# AJH_2b_v1_03.net
KiCad netlist of a schematic drawn in EAGLE
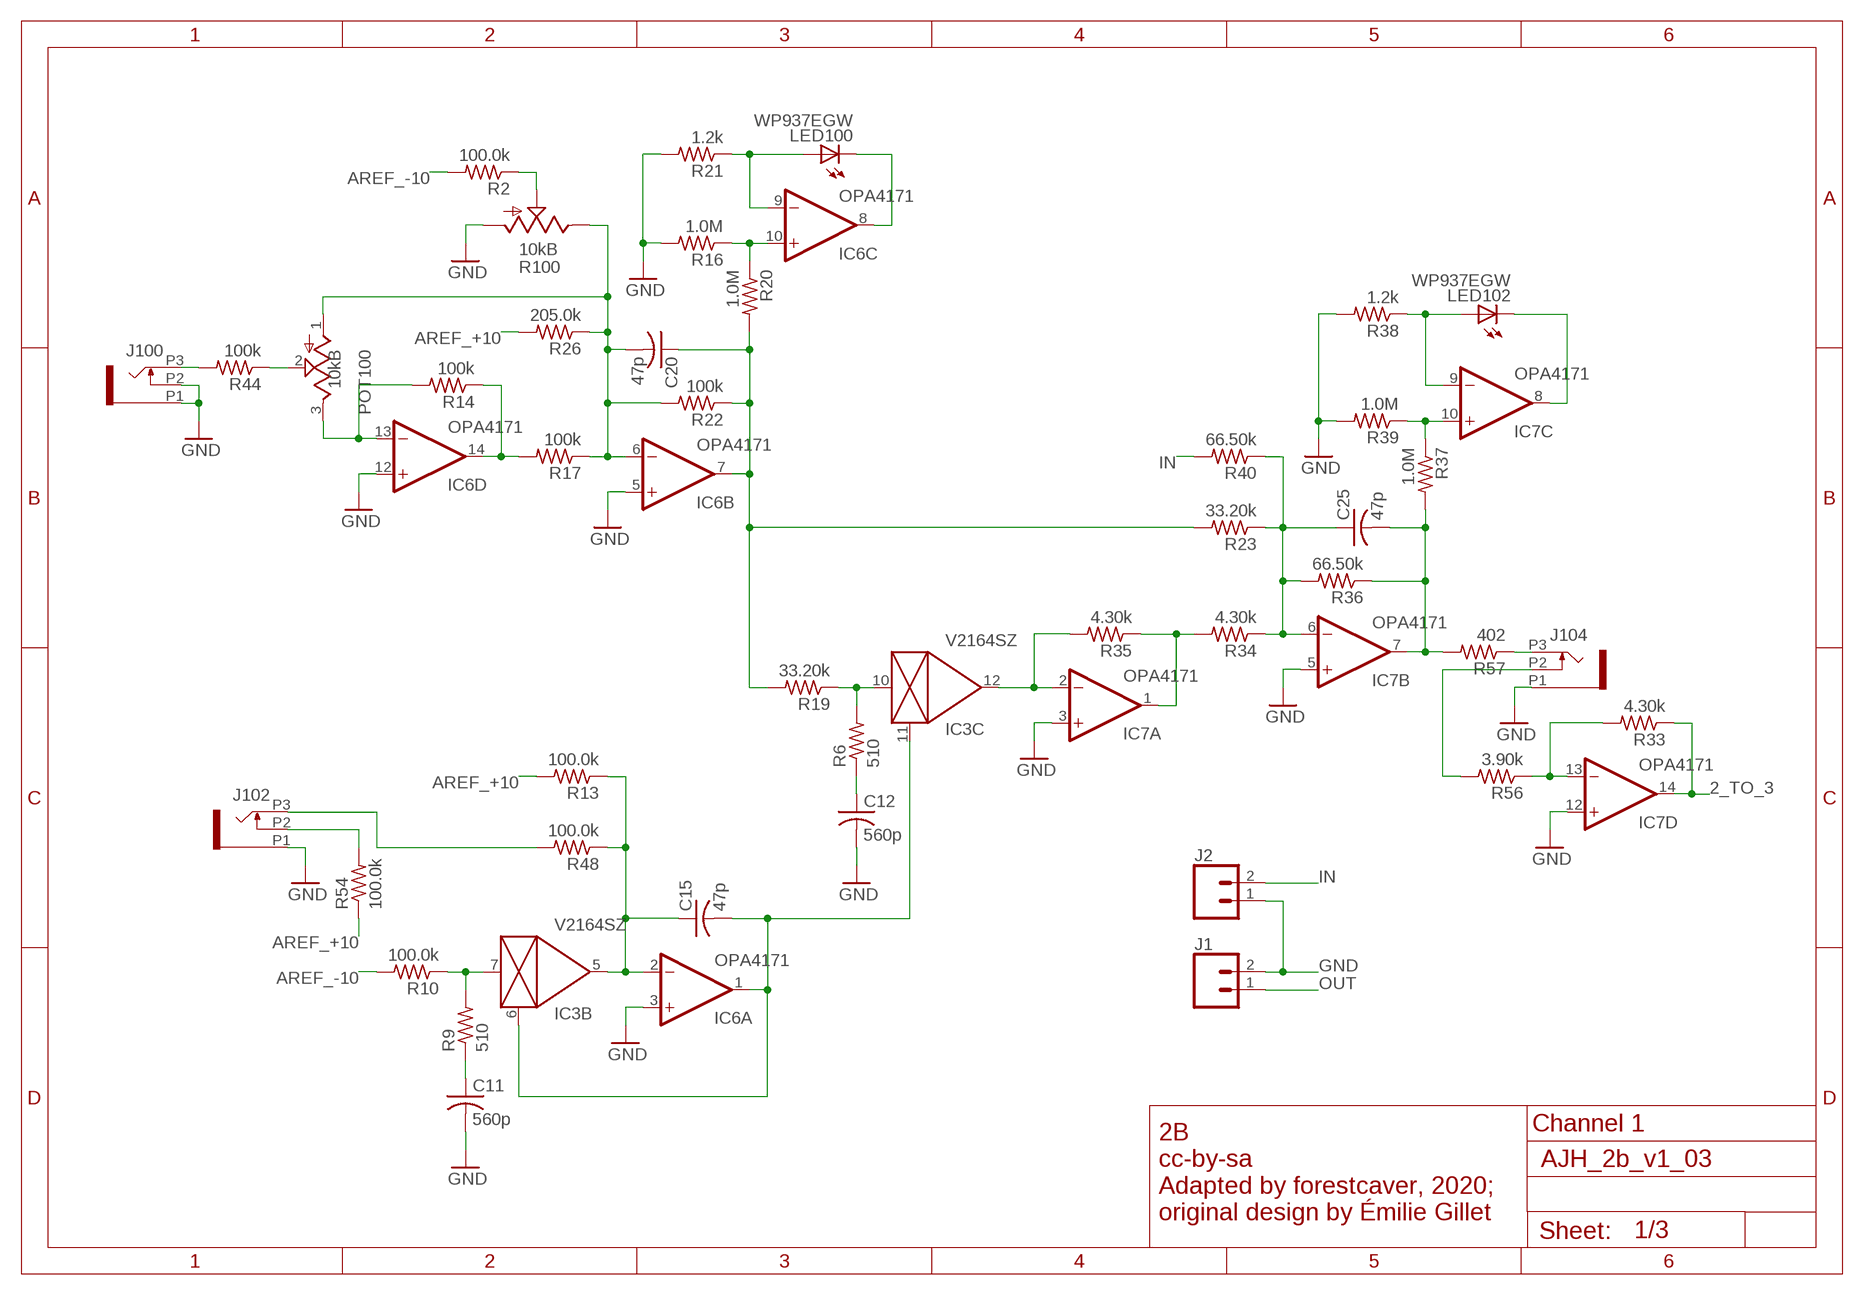
[diagram p0: schematic, sheet 1]
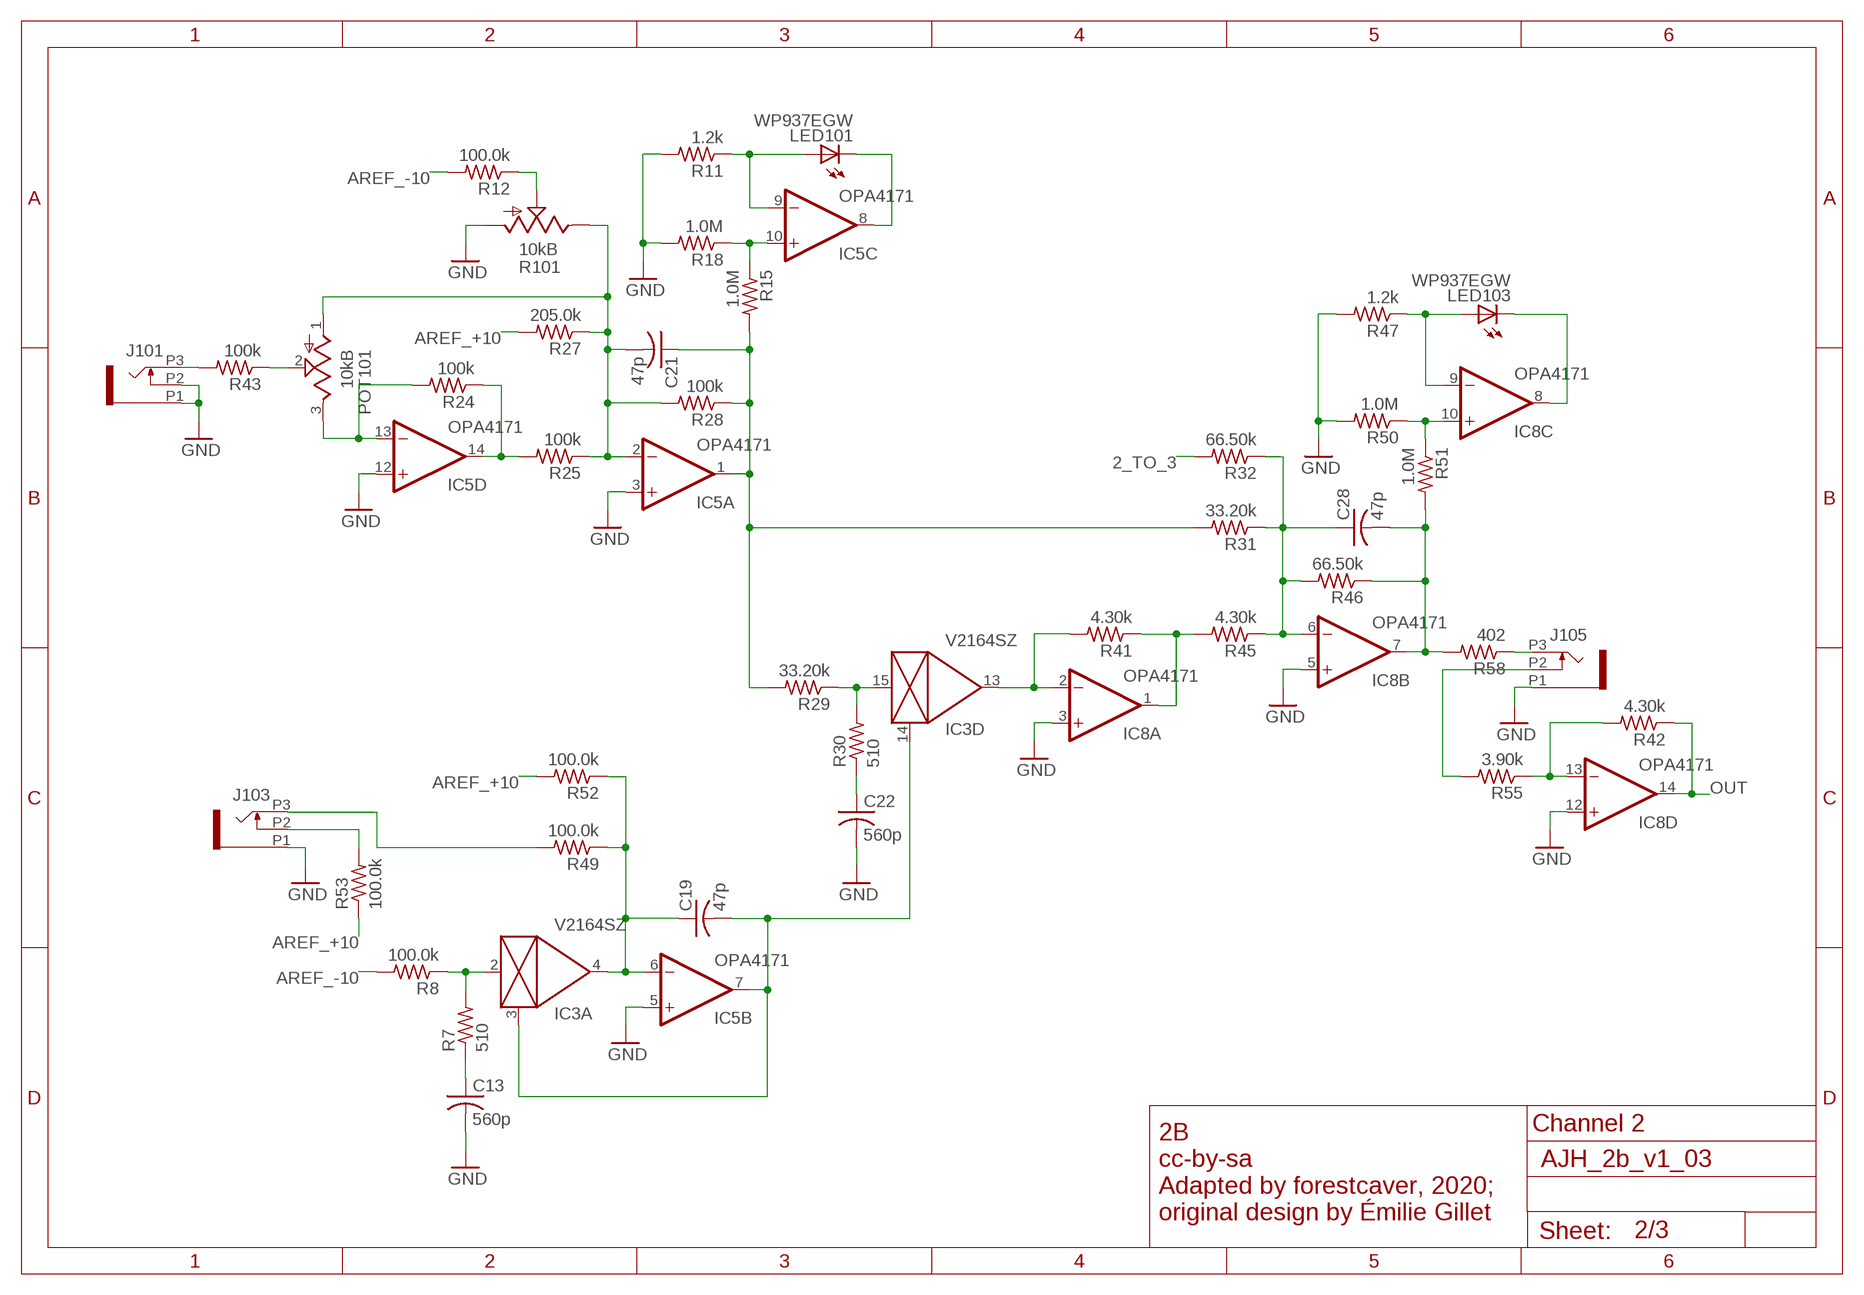
[diagram p1: schematic, sheet 2]
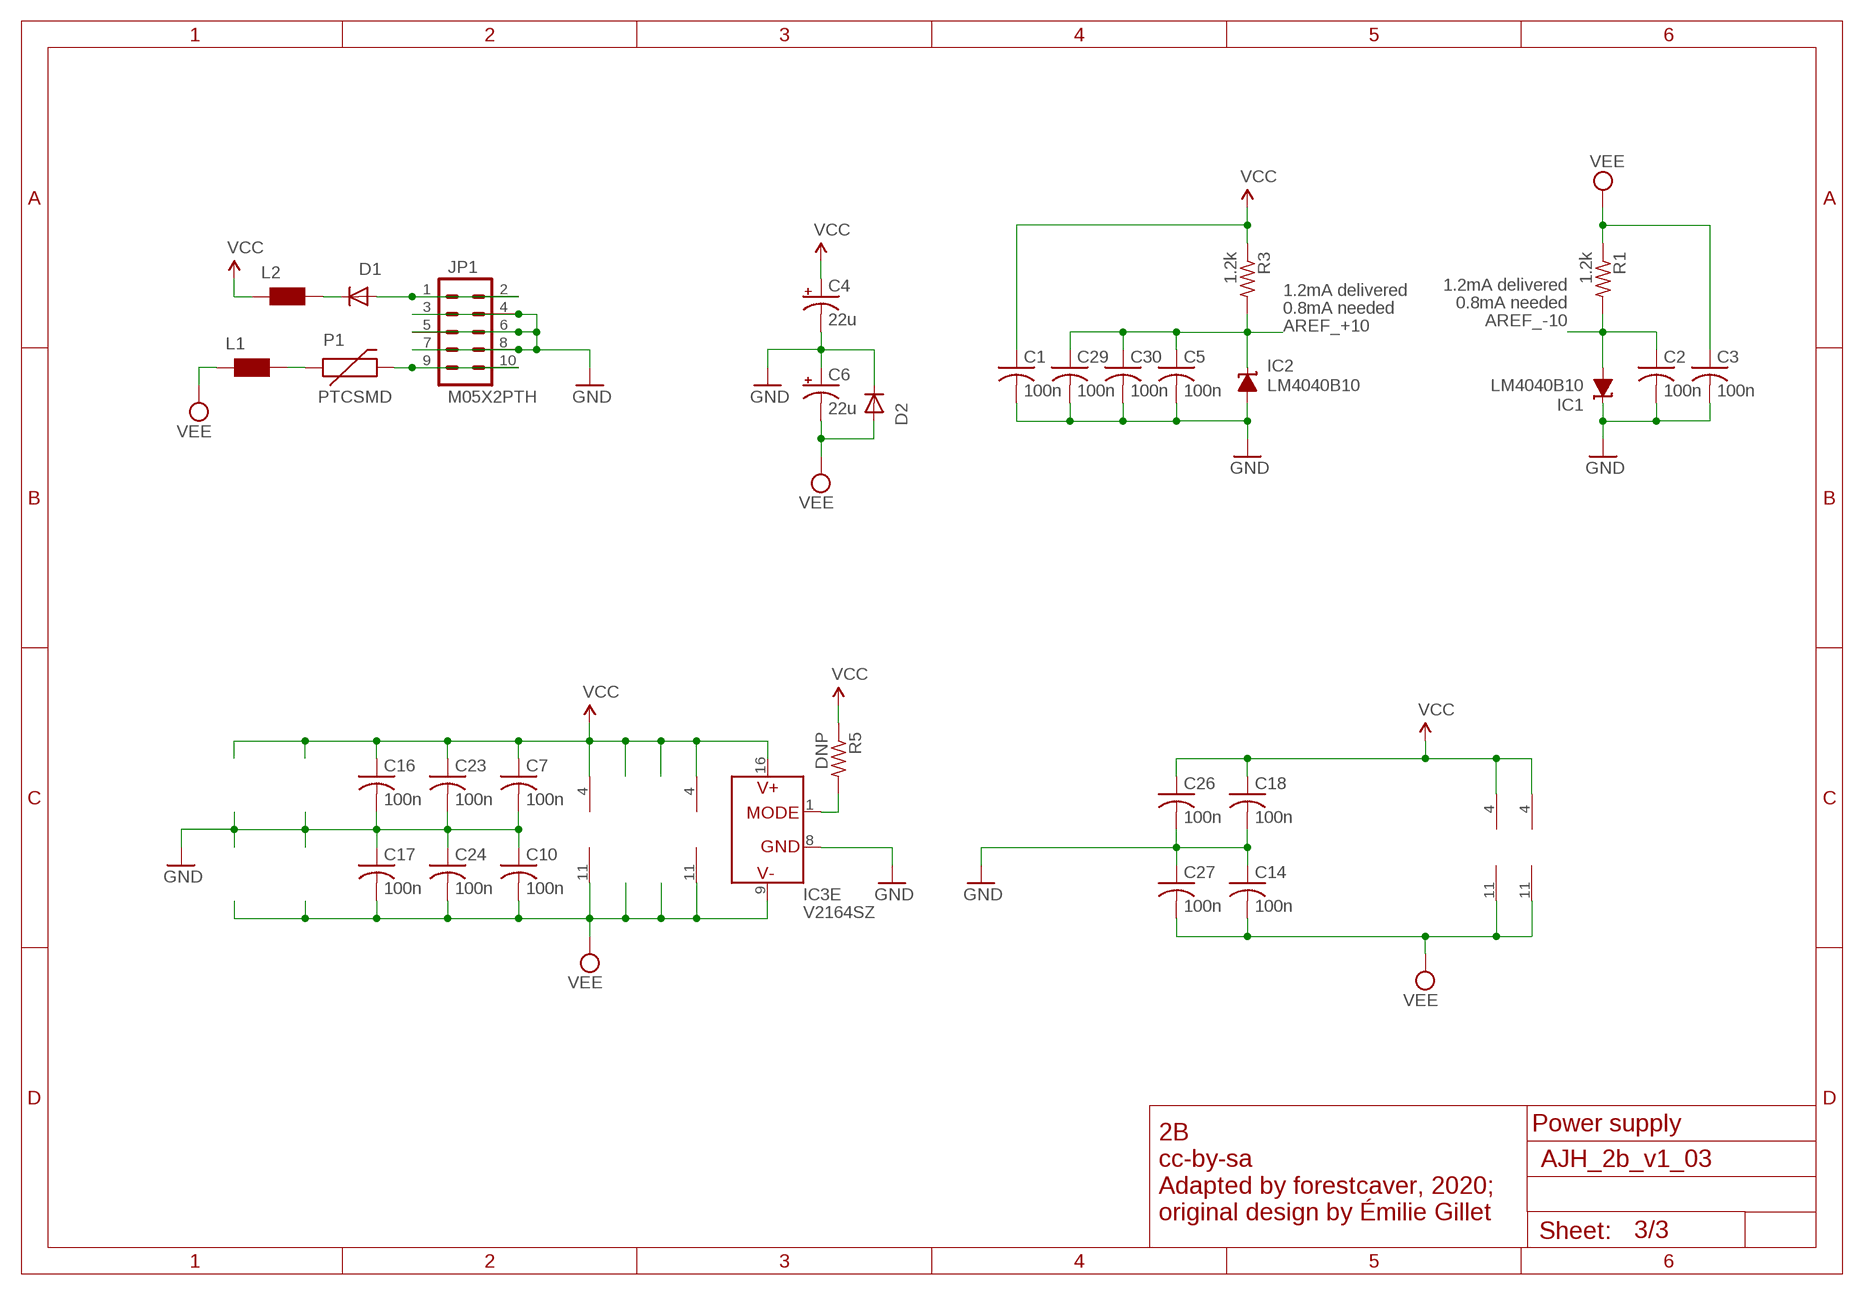
[diagram p2: schematic, sheet 3]

(export (version "E")
  (design (tool "Eeschema 10.0.6"))
  (components
    (comp (ref "C11")
      (value "560p")
      (footprint "eagle-import:C0402")
      (libsource (lib "eagle-import") (part "C-USC0402"))
    )
    (comp (ref "C12")
      (value "560p")
      (footprint "eagle-import:C0402")
      (libsource (lib "eagle-import") (part "C-USC0402"))
    )
    (comp (ref "C15")
      (value "47p")
      (footprint "eagle-import:C0402")
      (libsource (lib "eagle-import") (part "C-USC0402"))
    )
    (comp (ref "C20")
      (value "47p")
      (footprint "eagle-import:C0402")
      (libsource (lib "eagle-import") (part "C-USC0402"))
    )
    (comp (ref "C25")
      (value "47p")
      (footprint "eagle-import:C0402")
      (libsource (lib "eagle-import") (part "C-USC0402"))
    )
    (comp (ref "IC3")
      (value "V2164SZ")
      (footprint "eagle-import:SOIC16N")
      (libsource (lib "eagle-import") (part "SSM2164S"))
    )
    (comp (ref "IC6")
      (value "OPA4171")
      (footprint "eagle-import:TSSOP14")
      (libsource (lib "eagle-import") (part "TL074PW"))
    )
    (comp (ref "IC7")
      (value "OPA4171")
      (footprint "eagle-import:TSSOP14")
      (libsource (lib "eagle-import") (part "TL074PW"))
    )
    (comp (ref "J1")
      (value "CONN_02")
      (footprint "eagle-import:1X02")
      (libsource (lib "eagle-import") (part "CONN_02"))
    )
    (comp (ref "J2")
      (value "CONN_02")
      (footprint "eagle-import:1X02")
      (libsource (lib "eagle-import") (part "CONN_02"))
    )
    (comp (ref "J100")
      (value "PJ301_THONKICONN6")
      (footprint "eagle-import:WQP_PJ_301M6")
      (libsource (lib "eagle-import") (part "PJ301_THONKICONN6"))
    )
    (comp (ref "J102")
      (value "PJ301_THONKICONN6")
      (footprint "eagle-import:WQP_PJ_301M6")
      (libsource (lib "eagle-import") (part "PJ301_THONKICONN6"))
    )
    (comp (ref "J104")
      (value "PJ301_THONKICONN6")
      (footprint "eagle-import:WQP_PJ_301M6")
      (libsource (lib "eagle-import") (part "PJ301_THONKICONN6"))
    )
    (comp (ref "LED100")
      (value "WP937EGW")
      (footprint "eagle-import:LED3MM")
      (libsource (lib "eagle-import") (part "LED3MM"))
    )
    (comp (ref "LED102")
      (value "WP937EGW")
      (footprint "eagle-import:LED3MM")
      (libsource (lib "eagle-import") (part "LED3MM"))
    )
    (comp (ref "POT100")
      (value "10kB")
      (footprint "eagle-import:ALPS_POT_NOHOLE")
      (libsource (lib "eagle-import") (part "POT_VERTICALNOHOLE"))
    )
    (comp (ref "R2")
      (value "100.0k")
      (footprint "eagle-import:R0402")
      (libsource (lib "eagle-import") (part "R-US_R0402"))
    )
    (comp (ref "R6")
      (value "510")
      (footprint "eagle-import:R0402")
      (libsource (lib "eagle-import") (part "R-US_R0402"))
    )
    (comp (ref "R9")
      (value "510")
      (footprint "eagle-import:R0402")
      (libsource (lib "eagle-import") (part "R-US_R0402"))
    )
    (comp (ref "R10")
      (value "100.0k")
      (footprint "eagle-import:R0402")
      (libsource (lib "eagle-import") (part "R-US_R0402"))
    )
    (comp (ref "R13")
      (value "100.0k")
      (footprint "eagle-import:R0402")
      (libsource (lib "eagle-import") (part "R-US_R0402"))
    )
    (comp (ref "R14")
      (value "100k")
      (footprint "eagle-import:R0402")
      (libsource (lib "eagle-import") (part "R-US_R0402"))
    )
    (comp (ref "R16")
      (value "1.0M")
      (footprint "eagle-import:R0402")
      (libsource (lib "eagle-import") (part "R-US_R0402"))
    )
    (comp (ref "R17")
      (value "100k")
      (footprint "eagle-import:R0402")
      (libsource (lib "eagle-import") (part "R-US_R0402"))
    )
    (comp (ref "R19")
      (value "33.20k")
      (footprint "eagle-import:R0402")
      (libsource (lib "eagle-import") (part "R-US_R0402"))
    )
    (comp (ref "R20")
      (value "1.0M")
      (footprint "eagle-import:R0402")
      (libsource (lib "eagle-import") (part "R-US_R0402"))
    )
    (comp (ref "R21")
      (value "1.2k")
      (footprint "eagle-import:R0402")
      (libsource (lib "eagle-import") (part "R-US_R0402"))
    )
    (comp (ref "R22")
      (value "100k")
      (footprint "eagle-import:R0402")
      (libsource (lib "eagle-import") (part "R-US_R0402"))
    )
    (comp (ref "R23")
      (value "33.20k")
      (footprint "eagle-import:R0402")
      (libsource (lib "eagle-import") (part "R-US_R0402"))
    )
    (comp (ref "R26")
      (value "205.0k")
      (footprint "eagle-import:R0402")
      (libsource (lib "eagle-import") (part "R-US_R0402"))
    )
    (comp (ref "R33")
      (value "4.30k")
      (footprint "eagle-import:R0402")
      (libsource (lib "eagle-import") (part "R-US_R0402"))
    )
    (comp (ref "R34")
      (value "4.30k")
      (footprint "eagle-import:R0402")
      (libsource (lib "eagle-import") (part "R-US_R0402"))
    )
    (comp (ref "R35")
      (value "4.30k")
      (footprint "eagle-import:R0402")
      (libsource (lib "eagle-import") (part "R-US_R0402"))
    )
    (comp (ref "R36")
      (value "66.50k")
      (footprint "eagle-import:R0402")
      (libsource (lib "eagle-import") (part "R-US_R0402"))
    )
    (comp (ref "R37")
      (value "1.0M")
      (footprint "eagle-import:R0402")
      (libsource (lib "eagle-import") (part "R-US_R0402"))
    )
    (comp (ref "R38")
      (value "1.2k")
      (footprint "eagle-import:R0402")
      (libsource (lib "eagle-import") (part "R-US_R0402"))
    )
    (comp (ref "R39")
      (value "1.0M")
      (footprint "eagle-import:R0402")
      (libsource (lib "eagle-import") (part "R-US_R0402"))
    )
    (comp (ref "R40")
      (value "66.50k")
      (footprint "eagle-import:R0402")
      (libsource (lib "eagle-import") (part "R-US_R0402"))
    )
    (comp (ref "R44")
      (value "100k")
      (footprint "eagle-import:R0402")
      (libsource (lib "eagle-import") (part "R-US_R0402"))
    )
    (comp (ref "R48")
      (value "100.0k")
      (footprint "eagle-import:R0402")
      (libsource (lib "eagle-import") (part "R-US_R0402"))
    )
    (comp (ref "R54")
      (value "100.0k")
      (footprint "eagle-import:R0402")
      (libsource (lib "eagle-import") (part "R-US_R0402"))
    )
    (comp (ref "R56")
      (value "3.90k")
      (footprint "eagle-import:R0402")
      (libsource (lib "eagle-import") (part "R-US_R0402"))
    )
    (comp (ref "R57")
      (value "402")
      (footprint "eagle-import:R0402")
      (libsource (lib "eagle-import") (part "R-US_R0402"))
    )
    (comp (ref "R100")
      (value "10kB")
      (footprint "eagle-import:ALPS_POT_VERTICAL_PS")
      (libsource (lib "eagle-import") (part "POT_USVERTICAL_PS"))
    )
    (comp (ref "C1")
      (value "100n")
      (footprint "eagle-import:C0402")
      (libsource (lib "eagle-import") (part "C-USC0402"))
    )
    (comp (ref "C2")
      (value "100n")
      (footprint "eagle-import:C0402")
      (libsource (lib "eagle-import") (part "C-USC0402"))
    )
    (comp (ref "C3")
      (value "100n")
      (footprint "eagle-import:C0402")
      (libsource (lib "eagle-import") (part "C-USC0402"))
    )
    (comp (ref "C4")
      (value "22u")
      (footprint "eagle-import:PANASONIC_B")
      (libsource (lib "eagle-import") (part "CPOL-USB"))
    )
    (comp (ref "C5")
      (value "100n")
      (footprint "eagle-import:C0402")
      (libsource (lib "eagle-import") (part "C-USC0402"))
    )
    (comp (ref "C6")
      (value "22u")
      (footprint "eagle-import:PANASONIC_B")
      (libsource (lib "eagle-import") (part "CPOL-USB"))
    )
    (comp (ref "C7")
      (value "100n")
      (footprint "eagle-import:C0402")
      (libsource (lib "eagle-import") (part "C-USC0402"))
    )
    (comp (ref "C10")
      (value "100n")
      (footprint "eagle-import:C0402")
      (libsource (lib "eagle-import") (part "C-USC0402"))
    )
    (comp (ref "C14")
      (value "100n")
      (footprint "eagle-import:C0402")
      (libsource (lib "eagle-import") (part "C-USC0402"))
    )
    (comp (ref "C16")
      (value "100n")
      (footprint "eagle-import:C0402")
      (libsource (lib "eagle-import") (part "C-USC0402"))
    )
    (comp (ref "C17")
      (value "100n")
      (footprint "eagle-import:C0402")
      (libsource (lib "eagle-import") (part "C-USC0402"))
    )
    (comp (ref "C18")
      (value "100n")
      (footprint "eagle-import:C0402")
      (libsource (lib "eagle-import") (part "C-USC0402"))
    )
    (comp (ref "C23")
      (value "100n")
      (footprint "eagle-import:C0402")
      (libsource (lib "eagle-import") (part "C-USC0402"))
    )
    (comp (ref "C24")
      (value "100n")
      (footprint "eagle-import:C0402")
      (libsource (lib "eagle-import") (part "C-USC0402"))
    )
    (comp (ref "C26")
      (value "100n")
      (footprint "eagle-import:C0402")
      (libsource (lib "eagle-import") (part "C-USC0402"))
    )
    (comp (ref "C27")
      (value "100n")
      (footprint "eagle-import:C0402")
      (libsource (lib "eagle-import") (part "C-USC0402"))
    )
    (comp (ref "C29")
      (value "100n")
      (footprint "eagle-import:C0402")
      (libsource (lib "eagle-import") (part "C-USC0402"))
    )
    (comp (ref "C30")
      (value "100n")
      (footprint "eagle-import:C0402")
      (libsource (lib "eagle-import") (part "C-USC0402"))
    )
    (comp (ref "D1")
      (value "1N5819HW")
      (footprint "eagle-import:SOD123")
      (libsource (lib "eagle-import") (part "DIODE-SOD123"))
    )
    (comp (ref "D2")
      (value "1N5819HW")
      (footprint "eagle-import:SOD123")
      (libsource (lib "eagle-import") (part "DIODE-SOD123"))
    )
    (comp (ref "IC1")
      (value "LM4040B10")
      (footprint "eagle-import:DBZ_R-PDSO-G3")
      (libsource (lib "eagle-import") (part "LM4041DBZB12"))
    )
    (comp (ref "IC2")
      (value "LM4040B10")
      (footprint "eagle-import:DBZ_R-PDSO-G3")
      (libsource (lib "eagle-import") (part "LM4041DBZB12"))
    )
    (comp (ref "IC5")
      (value "OPA4171")
      (footprint "eagle-import:TSSOP14")
      (libsource (lib "eagle-import") (part "TL074PW"))
    )
    (comp (ref "IC8")
      (value "OPA4171")
      (footprint "eagle-import:TSSOP14")
      (libsource (lib "eagle-import") (part "TL074PW"))
    )
    (comp (ref "JP1")
      (value "M05X2PTH")
      (footprint "eagle-import:AVR_ICSP")
      (libsource (lib "eagle-import") (part "M05X2PTH"))
    )
    (comp (ref "L1")
      (value "WE-CBF_0603")
      (footprint "eagle-import:0603")
      (libsource (lib "eagle-import") (part "WE-CBF_0603"))
    )
    (comp (ref "L2")
      (value "WE-CBF_0603")
      (footprint "eagle-import:0603")
      (libsource (lib "eagle-import") (part "WE-CBF_0603"))
    )
    (comp (ref "P1")
      (value "PTCSMD")
      (footprint "eagle-import:PTC-1206")
      (libsource (lib "eagle-import") (part "PTCSMD"))
    )
    (comp (ref "R1")
      (value "1.2k")
      (footprint "eagle-import:R0402")
      (libsource (lib "eagle-import") (part "R-US_R0402"))
    )
    (comp (ref "R3")
      (value "1.2k")
      (footprint "eagle-import:R0402")
      (libsource (lib "eagle-import") (part "R-US_R0402"))
    )
    (comp (ref "R5")
      (value "DNP")
      (footprint "eagle-import:R0402")
      (libsource (lib "eagle-import") (part "R-US_R0402"))
    )
    (comp (ref "C13")
      (value "560p")
      (footprint "eagle-import:C0402")
      (libsource (lib "eagle-import") (part "C-USC0402"))
    )
    (comp (ref "C19")
      (value "47p")
      (footprint "eagle-import:C0402")
      (libsource (lib "eagle-import") (part "C-USC0402"))
    )
    (comp (ref "C21")
      (value "47p")
      (footprint "eagle-import:C0402")
      (libsource (lib "eagle-import") (part "C-USC0402"))
    )
    (comp (ref "C22")
      (value "560p")
      (footprint "eagle-import:C0402")
      (libsource (lib "eagle-import") (part "C-USC0402"))
    )
    (comp (ref "C28")
      (value "47p")
      (footprint "eagle-import:C0402")
      (libsource (lib "eagle-import") (part "C-USC0402"))
    )
    (comp (ref "J101")
      (value "PJ301_THONKICONN6")
      (footprint "eagle-import:WQP_PJ_301M6")
      (libsource (lib "eagle-import") (part "PJ301_THONKICONN6"))
    )
    (comp (ref "J103")
      (value "PJ301_THONKICONN6")
      (footprint "eagle-import:WQP_PJ_301M6")
      (libsource (lib "eagle-import") (part "PJ301_THONKICONN6"))
    )
    (comp (ref "J105")
      (value "PJ301_THONKICONN6")
      (footprint "eagle-import:WQP_PJ_301M6")
      (libsource (lib "eagle-import") (part "PJ301_THONKICONN6"))
    )
    (comp (ref "LED101")
      (value "WP937EGW")
      (footprint "eagle-import:LED3MM")
      (libsource (lib "eagle-import") (part "LED3MM"))
    )
    (comp (ref "LED103")
      (value "WP937EGW")
      (footprint "eagle-import:LED3MM")
      (libsource (lib "eagle-import") (part "LED3MM"))
    )
    (comp (ref "POT101")
      (value "10kB")
      (footprint "eagle-import:ALPS_POT_NOHOLE")
      (libsource (lib "eagle-import") (part "POT_VERTICALNOHOLE"))
    )
    (comp (ref "R7")
      (value "510")
      (footprint "eagle-import:R0402")
      (libsource (lib "eagle-import") (part "R-US_R0402"))
    )
    (comp (ref "R8")
      (value "100.0k")
      (footprint "eagle-import:R0402")
      (libsource (lib "eagle-import") (part "R-US_R0402"))
    )
    (comp (ref "R11")
      (value "1.2k")
      (footprint "eagle-import:R0402")
      (libsource (lib "eagle-import") (part "R-US_R0402"))
    )
    (comp (ref "R12")
      (value "100.0k")
      (footprint "eagle-import:R0402")
      (libsource (lib "eagle-import") (part "R-US_R0402"))
    )
    (comp (ref "R15")
      (value "1.0M")
      (footprint "eagle-import:R0402")
      (libsource (lib "eagle-import") (part "R-US_R0402"))
    )
    (comp (ref "R18")
      (value "1.0M")
      (footprint "eagle-import:R0402")
      (libsource (lib "eagle-import") (part "R-US_R0402"))
    )
    (comp (ref "R24")
      (value "100k")
      (footprint "eagle-import:R0402")
      (libsource (lib "eagle-import") (part "R-US_R0402"))
    )
    (comp (ref "R25")
      (value "100k")
      (footprint "eagle-import:R0402")
      (libsource (lib "eagle-import") (part "R-US_R0402"))
    )
    (comp (ref "R27")
      (value "205.0k")
      (footprint "eagle-import:R0402")
      (libsource (lib "eagle-import") (part "R-US_R0402"))
    )
    (comp (ref "R28")
      (value "100k")
      (footprint "eagle-import:R0402")
      (libsource (lib "eagle-import") (part "R-US_R0402"))
    )
    (comp (ref "R29")
      (value "33.20k")
      (footprint "eagle-import:R0402")
      (libsource (lib "eagle-import") (part "R-US_R0402"))
    )
    (comp (ref "R30")
      (value "510")
      (footprint "eagle-import:R0402")
      (libsource (lib "eagle-import") (part "R-US_R0402"))
    )
    (comp (ref "R31")
      (value "33.20k")
      (footprint "eagle-import:R0402")
      (libsource (lib "eagle-import") (part "R-US_R0402"))
    )
    (comp (ref "R32")
      (value "66.50k")
      (footprint "eagle-import:R0402")
      (libsource (lib "eagle-import") (part "R-US_R0402"))
    )
    (comp (ref "R41")
      (value "4.30k")
      (footprint "eagle-import:R0402")
      (libsource (lib "eagle-import") (part "R-US_R0402"))
    )
    (comp (ref "R42")
      (value "4.30k")
      (footprint "eagle-import:R0402")
      (libsource (lib "eagle-import") (part "R-US_R0402"))
    )
    (comp (ref "R43")
      (value "100k")
      (footprint "eagle-import:R0402")
      (libsource (lib "eagle-import") (part "R-US_R0402"))
    )
    (comp (ref "R45")
      (value "4.30k")
      (footprint "eagle-import:R0402")
      (libsource (lib "eagle-import") (part "R-US_R0402"))
    )
    (comp (ref "R46")
      (value "66.50k")
      (footprint "eagle-import:R0402")
      (libsource (lib "eagle-import") (part "R-US_R0402"))
    )
    (comp (ref "R47")
      (value "1.2k")
      (footprint "eagle-import:R0402")
      (libsource (lib "eagle-import") (part "R-US_R0402"))
    )
    (comp (ref "R49")
      (value "100.0k")
      (footprint "eagle-import:R0402")
      (libsource (lib "eagle-import") (part "R-US_R0402"))
    )
    (comp (ref "R50")
      (value "1.0M")
      (footprint "eagle-import:R0402")
      (libsource (lib "eagle-import") (part "R-US_R0402"))
    )
    (comp (ref "R51")
      (value "1.0M")
      (footprint "eagle-import:R0402")
      (libsource (lib "eagle-import") (part "R-US_R0402"))
    )
    (comp (ref "R52")
      (value "100.0k")
      (footprint "eagle-import:R0402")
      (libsource (lib "eagle-import") (part "R-US_R0402"))
    )
    (comp (ref "R53")
      (value "100.0k")
      (footprint "eagle-import:R0402")
      (libsource (lib "eagle-import") (part "R-US_R0402"))
    )
    (comp (ref "R55")
      (value "3.90k")
      (footprint "eagle-import:R0402")
      (libsource (lib "eagle-import") (part "R-US_R0402"))
    )
    (comp (ref "R58")
      (value "402")
      (footprint "eagle-import:R0402")
      (libsource (lib "eagle-import") (part "R-US_R0402"))
    )
    (comp (ref "R101")
      (value "10kB")
      (footprint "eagle-import:ALPS_POT_VERTICAL_PS")
      (libsource (lib "eagle-import") (part "POT_USVERTICAL_PS"))
    )
  )
  (nets
    (net (code "1") (name "2_TO_3") (class "Default")
      (node (ref "IC7") (pin "14") (pinfunction "OUT_14") (pintype "output"))
      (node (ref "R32") (pin "2") (pinfunction "2_2") (pintype "passive"))
      (node (ref "R33") (pin "1") (pinfunction "1_1") (pintype "passive"))
    )
    (net (code "2") (name "AREF_+10") (class "Default")
      (node (ref "C29") (pin "1") (pinfunction "1_1") (pintype "passive"))
      (node (ref "C30") (pin "1") (pinfunction "1_1") (pintype "passive"))
      (node (ref "C5") (pin "1") (pinfunction "1_1") (pintype "passive"))
      (node (ref "IC2") (pin "1") (pinfunction "C_1") (pintype "passive"))
      (node (ref "R13") (pin "2") (pinfunction "2_2") (pintype "passive"))
      (node (ref "R26") (pin "2") (pinfunction "2_2") (pintype "passive"))
      (node (ref "R27") (pin "2") (pinfunction "2_2") (pintype "passive"))
      (node (ref "R3") (pin "2") (pinfunction "2_2") (pintype "passive"))
      (node (ref "R52") (pin "2") (pinfunction "2_2") (pintype "passive"))
      (node (ref "R53") (pin "1") (pinfunction "1_1") (pintype "passive"))
      (node (ref "R54") (pin "1") (pinfunction "1_1") (pintype "passive"))
    )
    (net (code "3") (name "AREF_-10") (class "Default")
      (node (ref "C2") (pin "1") (pinfunction "1_1") (pintype "passive"))
      (node (ref "IC1") (pin "2") (pinfunction "A_2") (pintype "passive"))
      (node (ref "R1") (pin "2") (pinfunction "2_2") (pintype "passive"))
      (node (ref "R10") (pin "2") (pinfunction "2_2") (pintype "passive"))
      (node (ref "R12") (pin "2") (pinfunction "2_2") (pintype "passive"))
      (node (ref "R2") (pin "2") (pinfunction "2_2") (pintype "passive"))
      (node (ref "R8") (pin "2") (pinfunction "2_2") (pintype "passive"))
    )
    (net (code "4") (name "GND") (class "Default")
      (node (ref "C1") (pin "2") (pinfunction "2_2") (pintype "passive"))
      (node (ref "C10") (pin "1") (pinfunction "1_1") (pintype "passive"))
      (node (ref "C11") (pin "2") (pinfunction "2_2") (pintype "passive"))
      (node (ref "C12") (pin "2") (pinfunction "2_2") (pintype "passive"))
      (node (ref "C13") (pin "2") (pinfunction "2_2") (pintype "passive"))
      (node (ref "C14") (pin "1") (pinfunction "1_1") (pintype "passive"))
      (node (ref "C16") (pin "2") (pinfunction "2_2") (pintype "passive"))
      (node (ref "C17") (pin "1") (pinfunction "1_1") (pintype "passive"))
      (node (ref "C18") (pin "2") (pinfunction "2_2") (pintype "passive"))
      (node (ref "C2") (pin "2") (pinfunction "2_2") (pintype "passive"))
      (node (ref "C22") (pin "2") (pinfunction "2_2") (pintype "passive"))
      (node (ref "C23") (pin "2") (pinfunction "2_2") (pintype "passive"))
      (node (ref "C24") (pin "1") (pinfunction "1_1") (pintype "passive"))
      (node (ref "C26") (pin "2") (pinfunction "2_2") (pintype "passive"))
      (node (ref "C27") (pin "1") (pinfunction "1_1") (pintype "passive"))
      (node (ref "C29") (pin "2") (pinfunction "2_2") (pintype "passive"))
      (node (ref "C3") (pin "2") (pinfunction "2_2") (pintype "passive"))
      (node (ref "C30") (pin "2") (pinfunction "2_2") (pintype "passive"))
      (node (ref "C4") (pin "-") (pinfunction "-_-") (pintype "passive"))
      (node (ref "C5") (pin "2") (pinfunction "2_2") (pintype "passive"))
      (node (ref "C6") (pin "+") (pinfunction "+_+") (pintype "passive"))
      (node (ref "C7") (pin "2") (pinfunction "2_2") (pintype "passive"))
      (node (ref "D2") (pin "C") (pinfunction "C_C") (pintype "passive"))
      (node (ref "IC1") (pin "1") (pinfunction "C_1") (pintype "passive"))
      (node (ref "IC2") (pin "2") (pinfunction "A_2") (pintype "passive"))
      (node (ref "IC3") (pin "8") (pinfunction "GND_8") (pintype "power_in"))
      (node (ref "IC5") (pin "12") (pinfunction "+IN_12") (pintype "input"))
      (node (ref "IC5") (pin "3") (pinfunction "+IN_3") (pintype "input"))
      (node (ref "IC5") (pin "5") (pinfunction "+IN_5") (pintype "input"))
      (node (ref "IC6") (pin "12") (pinfunction "+IN_12") (pintype "input"))
      (node (ref "IC6") (pin "3") (pinfunction "+IN_3") (pintype "input"))
      (node (ref "IC6") (pin "5") (pinfunction "+IN_5") (pintype "input"))
      (node (ref "IC7") (pin "12") (pinfunction "+IN_12") (pintype "input"))
      (node (ref "IC7") (pin "3") (pinfunction "+IN_3") (pintype "input"))
      (node (ref "IC7") (pin "5") (pinfunction "+IN_5") (pintype "input"))
      (node (ref "IC8") (pin "12") (pinfunction "+IN_12") (pintype "input"))
      (node (ref "IC8") (pin "3") (pinfunction "+IN_3") (pintype "input"))
      (node (ref "IC8") (pin "5") (pinfunction "+IN_5") (pintype "input"))
      (node (ref "J1") (pin "2") (pinfunction "2_2") (pintype "passive"))
      (node (ref "J100") (pin "P1") (pinfunction "1_P1") (pintype "passive"))
      (node (ref "J100") (pin "P2") (pinfunction "2_P2") (pintype "passive"))
      (node (ref "J101") (pin "P1") (pinfunction "1_P1") (pintype "passive"))
      (node (ref "J101") (pin "P2") (pinfunction "2_P2") (pintype "passive"))
      (node (ref "J102") (pin "P1") (pinfunction "1_P1") (pintype "passive"))
      (node (ref "J103") (pin "P1") (pinfunction "1_P1") (pintype "passive"))
      (node (ref "J104") (pin "P1") (pinfunction "1_P1") (pintype "passive"))
      (node (ref "J105") (pin "P1") (pinfunction "1_P1") (pintype "passive"))
      (node (ref "J2") (pin "1") (pinfunction "1_1") (pintype "passive"))
      (node (ref "JP1") (pin "3") (pinfunction "3_3") (pintype "passive"))
      (node (ref "JP1") (pin "4") (pinfunction "4_4") (pintype "passive"))
      (node (ref "JP1") (pin "5") (pinfunction "5_5") (pintype "passive"))
      (node (ref "JP1") (pin "6") (pinfunction "6_6") (pintype "passive"))
      (node (ref "JP1") (pin "7") (pinfunction "7_7") (pintype "passive"))
      (node (ref "JP1") (pin "8") (pinfunction "8_8") (pintype "passive"))
      (node (ref "R100") (pin "P$3") (pinfunction "A_P$3") (pintype "passive"))
      (node (ref "R101") (pin "P$3") (pinfunction "A_P$3") (pintype "passive"))
      (node (ref "R11") (pin "2") (pinfunction "2_2") (pintype "passive"))
      (node (ref "R16") (pin "2") (pinfunction "2_2") (pintype "passive"))
      (node (ref "R18") (pin "2") (pinfunction "2_2") (pintype "passive"))
      (node (ref "R21") (pin "2") (pinfunction "2_2") (pintype "passive"))
      (node (ref "R38") (pin "2") (pinfunction "2_2") (pintype "passive"))
      (node (ref "R39") (pin "2") (pinfunction "2_2") (pintype "passive"))
      (node (ref "R47") (pin "2") (pinfunction "2_2") (pintype "passive"))
      (node (ref "R50") (pin "2") (pinfunction "2_2") (pintype "passive"))
    )
    (net (code "5") (name "IN") (class "Default")
      (node (ref "J2") (pin "2") (pinfunction "2_2") (pintype "passive"))
      (node (ref "R40") (pin "2") (pinfunction "2_2") (pintype "passive"))
    )
    (net (code "6") (name "Net-(C11-Pad1)") (class "Default")
      (node (ref "C11") (pin "1") (pinfunction "1_1") (pintype "passive"))
      (node (ref "R9") (pin "1") (pinfunction "1_1") (pintype "passive"))
    )
    (net (code "7") (name "Net-(C12-Pad1)") (class "Default")
      (node (ref "C12") (pin "1") (pinfunction "1_1") (pintype "passive"))
      (node (ref "R6") (pin "1") (pinfunction "1_1") (pintype "passive"))
    )
    (net (code "8") (name "Net-(C13-Pad1)") (class "Default")
      (node (ref "C13") (pin "1") (pinfunction "1_1") (pintype "passive"))
      (node (ref "R7") (pin "1") (pinfunction "1_1") (pintype "passive"))
    )
    (net (code "9") (name "Net-(C22-Pad1)") (class "Default")
      (node (ref "C22") (pin "1") (pinfunction "1_1") (pintype "passive"))
      (node (ref "R30") (pin "1") (pinfunction "1_1") (pintype "passive"))
    )
    (net (code "10") (name "Net-(D1-PadA)") (class "Default")
      (node (ref "D1") (pin "A") (pinfunction "A_A") (pintype "passive"))
      (node (ref "JP1") (pin "1") (pinfunction "1_1") (pintype "passive"))
      (node (ref "JP1") (pin "2") (pinfunction "2_2") (pintype "passive"))
    )
    (net (code "11") (name "Net-(D1-PadC)") (class "Default")
      (node (ref "D1") (pin "C") (pinfunction "C_C") (pintype "passive"))
      (node (ref "L2") (pin "2") (pinfunction "2_2") (pintype "passive"))
    )
    (net (code "12") (name "Net-(IC3A-CTRL)") (class "Default")
      (node (ref "C19") (pin "2") (pinfunction "2_2") (pintype "passive"))
      (node (ref "IC3") (pin "14") (pinfunction "CTRL_14") (pintype "input"))
      (node (ref "IC3") (pin "3") (pinfunction "CTRL_3") (pintype "input"))
      (node (ref "IC5") (pin "7") (pinfunction "OUT_7") (pintype "output"))
    )
    (net (code "13") (name "Net-(IC3A-IN)") (class "Default")
      (node (ref "IC3") (pin "2") (pinfunction "IN_2") (pintype "input"))
      (node (ref "R7") (pin "2") (pinfunction "2_2") (pintype "passive"))
      (node (ref "R8") (pin "1") (pinfunction "1_1") (pintype "passive"))
    )
    (net (code "14") (name "Net-(IC3A-OUT)") (class "Default")
      (node (ref "C19") (pin "1") (pinfunction "1_1") (pintype "passive"))
      (node (ref "IC3") (pin "4") (pinfunction "OUT_4") (pintype "output"))
      (node (ref "IC5") (pin "6") (pinfunction "-IN_6") (pintype "input"))
      (node (ref "R49") (pin "1") (pinfunction "1_1") (pintype "passive"))
      (node (ref "R52") (pin "1") (pinfunction "1_1") (pintype "passive"))
    )
    (net (code "15") (name "Net-(IC3B-CTRL)") (class "Default")
      (node (ref "C15") (pin "2") (pinfunction "2_2") (pintype "passive"))
      (node (ref "IC3") (pin "11") (pinfunction "CTRL_11") (pintype "input"))
      (node (ref "IC3") (pin "6") (pinfunction "CTRL_6") (pintype "input"))
      (node (ref "IC6") (pin "1") (pinfunction "OUT_1") (pintype "output"))
    )
    (net (code "16") (name "Net-(IC3B-IN)") (class "Default")
      (node (ref "IC3") (pin "7") (pinfunction "IN_7") (pintype "input"))
      (node (ref "R10") (pin "1") (pinfunction "1_1") (pintype "passive"))
      (node (ref "R9") (pin "2") (pinfunction "2_2") (pintype "passive"))
    )
    (net (code "17") (name "Net-(IC3B-OUT)") (class "Default")
      (node (ref "C15") (pin "1") (pinfunction "1_1") (pintype "passive"))
      (node (ref "IC3") (pin "5") (pinfunction "OUT_5") (pintype "output"))
      (node (ref "IC6") (pin "2") (pinfunction "-IN_2") (pintype "input"))
      (node (ref "R13") (pin "1") (pinfunction "1_1") (pintype "passive"))
      (node (ref "R48") (pin "1") (pinfunction "1_1") (pintype "passive"))
    )
    (net (code "18") (name "Net-(IC3C-IN)") (class "Default")
      (node (ref "IC3") (pin "10") (pinfunction "IN_10") (pintype "input"))
      (node (ref "R19") (pin "1") (pinfunction "1_1") (pintype "passive"))
      (node (ref "R6") (pin "2") (pinfunction "2_2") (pintype "passive"))
    )
    (net (code "19") (name "Net-(IC3C-OUT)") (class "Default")
      (node (ref "IC3") (pin "12") (pinfunction "OUT_12") (pintype "output"))
      (node (ref "IC7") (pin "2") (pinfunction "-IN_2") (pintype "input"))
      (node (ref "R35") (pin "2") (pinfunction "2_2") (pintype "passive"))
    )
    (net (code "20") (name "Net-(IC3D-IN)") (class "Default")
      (node (ref "IC3") (pin "15") (pinfunction "IN_15") (pintype "input"))
      (node (ref "R29") (pin "1") (pinfunction "1_1") (pintype "passive"))
      (node (ref "R30") (pin "2") (pinfunction "2_2") (pintype "passive"))
    )
    (net (code "21") (name "Net-(IC3D-OUT)") (class "Default")
      (node (ref "IC3") (pin "13") (pinfunction "OUT_13") (pintype "output"))
      (node (ref "IC8") (pin "2") (pinfunction "-IN_2") (pintype "input"))
      (node (ref "R41") (pin "2") (pinfunction "2_2") (pintype "passive"))
    )
    (net (code "22") (name "Net-(IC3E-MODE)") (class "Default")
      (node (ref "IC3") (pin "1") (pinfunction "MODE_1") (pintype "input"))
      (node (ref "R5") (pin "2") (pinfunction "2_2") (pintype "passive"))
    )
    (net (code "23") (name "Net-(IC5A--IN)") (class "Default")
      (node (ref "C21") (pin "2") (pinfunction "2_2") (pintype "passive"))
      (node (ref "IC5") (pin "2") (pinfunction "-IN_2") (pintype "input"))
      (node (ref "POT101") (pin "1") (pinfunction "A_1") (pintype "passive"))
      (node (ref "R101") (pin "P$1") (pinfunction "E_P$1") (pintype "passive"))
      (node (ref "R25") (pin "1") (pinfunction "1_1") (pintype "passive"))
      (node (ref "R27") (pin "1") (pinfunction "1_1") (pintype "passive"))
      (node (ref "R28") (pin "2") (pinfunction "2_2") (pintype "passive"))
    )
    (net (code "24") (name "Net-(IC5A-OUT)") (class "Default")
      (node (ref "C21") (pin "1") (pinfunction "1_1") (pintype "passive"))
      (node (ref "IC5") (pin "1") (pinfunction "OUT_1") (pintype "output"))
      (node (ref "R15") (pin "2") (pinfunction "2_2") (pintype "passive"))
      (node (ref "R28") (pin "1") (pinfunction "1_1") (pintype "passive"))
      (node (ref "R29") (pin "2") (pinfunction "2_2") (pintype "passive"))
      (node (ref "R31") (pin "2") (pinfunction "2_2") (pintype "passive"))
    )
    (net (code "25") (name "Net-(IC5C-+IN)") (class "Default")
      (node (ref "IC5") (pin "10") (pinfunction "+IN_10") (pintype "input"))
      (node (ref "R15") (pin "1") (pinfunction "1_1") (pintype "passive"))
      (node (ref "R18") (pin "1") (pinfunction "1_1") (pintype "passive"))
    )
    (net (code "26") (name "Net-(IC5C--IN)") (class "Default")
      (node (ref "IC5") (pin "9") (pinfunction "-IN_9") (pintype "input"))
      (node (ref "LED101") (pin "A") (pinfunction "A_A") (pintype "passive"))
      (node (ref "R11") (pin "1") (pinfunction "1_1") (pintype "passive"))
    )
    (net (code "27") (name "Net-(IC5C-OUT)") (class "Default")
      (node (ref "IC5") (pin "8") (pinfunction "OUT_8") (pintype "output"))
      (node (ref "LED101") (pin "K") (pinfunction "C_K") (pintype "passive"))
    )
    (net (code "28") (name "Net-(IC5D--IN)") (class "Default")
      (node (ref "IC5") (pin "13") (pinfunction "-IN_13") (pintype "input"))
      (node (ref "POT101") (pin "3") (pinfunction "B_3") (pintype "passive"))
      (node (ref "R24") (pin "2") (pinfunction "2_2") (pintype "passive"))
    )
    (net (code "29") (name "Net-(IC5D-OUT)") (class "Default")
      (node (ref "IC5") (pin "14") (pinfunction "OUT_14") (pintype "output"))
      (node (ref "R24") (pin "1") (pinfunction "1_1") (pintype "passive"))
      (node (ref "R25") (pin "2") (pinfunction "2_2") (pintype "passive"))
    )
    (net (code "30") (name "Net-(IC6B--IN)") (class "Default")
      (node (ref "C20") (pin "2") (pinfunction "2_2") (pintype "passive"))
      (node (ref "IC6") (pin "6") (pinfunction "-IN_6") (pintype "input"))
      (node (ref "POT100") (pin "1") (pinfunction "A_1") (pintype "passive"))
      (node (ref "R100") (pin "P$1") (pinfunction "E_P$1") (pintype "passive"))
      (node (ref "R17") (pin "1") (pinfunction "1_1") (pintype "passive"))
      (node (ref "R22") (pin "2") (pinfunction "2_2") (pintype "passive"))
      (node (ref "R26") (pin "1") (pinfunction "1_1") (pintype "passive"))
    )
    (net (code "31") (name "Net-(IC6B-OUT)") (class "Default")
      (node (ref "C20") (pin "1") (pinfunction "1_1") (pintype "passive"))
      (node (ref "IC6") (pin "7") (pinfunction "OUT_7") (pintype "output"))
      (node (ref "R19") (pin "2") (pinfunction "2_2") (pintype "passive"))
      (node (ref "R20") (pin "2") (pinfunction "2_2") (pintype "passive"))
      (node (ref "R22") (pin "1") (pinfunction "1_1") (pintype "passive"))
      (node (ref "R23") (pin "2") (pinfunction "2_2") (pintype "passive"))
    )
    (net (code "32") (name "Net-(IC6C-+IN)") (class "Default")
      (node (ref "IC6") (pin "10") (pinfunction "+IN_10") (pintype "input"))
      (node (ref "R16") (pin "1") (pinfunction "1_1") (pintype "passive"))
      (node (ref "R20") (pin "1") (pinfunction "1_1") (pintype "passive"))
    )
    (net (code "33") (name "Net-(IC6C--IN)") (class "Default")
      (node (ref "IC6") (pin "9") (pinfunction "-IN_9") (pintype "input"))
      (node (ref "LED100") (pin "A") (pinfunction "A_A") (pintype "passive"))
      (node (ref "R21") (pin "1") (pinfunction "1_1") (pintype "passive"))
    )
    (net (code "34") (name "Net-(IC6C-OUT)") (class "Default")
      (node (ref "IC6") (pin "8") (pinfunction "OUT_8") (pintype "output"))
      (node (ref "LED100") (pin "K") (pinfunction "C_K") (pintype "passive"))
    )
    (net (code "35") (name "Net-(IC6D--IN)") (class "Default")
      (node (ref "IC6") (pin "13") (pinfunction "-IN_13") (pintype "input"))
      (node (ref "POT100") (pin "3") (pinfunction "B_3") (pintype "passive"))
      (node (ref "R14") (pin "2") (pinfunction "2_2") (pintype "passive"))
    )
    (net (code "36") (name "Net-(IC6D-OUT)") (class "Default")
      (node (ref "IC6") (pin "14") (pinfunction "OUT_14") (pintype "output"))
      (node (ref "R14") (pin "1") (pinfunction "1_1") (pintype "passive"))
      (node (ref "R17") (pin "2") (pinfunction "2_2") (pintype "passive"))
    )
    (net (code "37") (name "Net-(IC7A-OUT)") (class "Default")
      (node (ref "IC7") (pin "1") (pinfunction "OUT_1") (pintype "output"))
      (node (ref "R34") (pin "2") (pinfunction "2_2") (pintype "passive"))
      (node (ref "R35") (pin "1") (pinfunction "1_1") (pintype "passive"))
    )
    (net (code "38") (name "Net-(IC7B--IN)") (class "Default")
      (node (ref "C25") (pin "1") (pinfunction "1_1") (pintype "passive"))
      (node (ref "IC7") (pin "6") (pinfunction "-IN_6") (pintype "input"))
      (node (ref "R23") (pin "1") (pinfunction "1_1") (pintype "passive"))
      (node (ref "R34") (pin "1") (pinfunction "1_1") (pintype "passive"))
      (node (ref "R36") (pin "2") (pinfunction "2_2") (pintype "passive"))
      (node (ref "R40") (pin "1") (pinfunction "1_1") (pintype "passive"))
    )
    (net (code "39") (name "Net-(IC7B-OUT)") (class "Default")
      (node (ref "C25") (pin "2") (pinfunction "2_2") (pintype "passive"))
      (node (ref "IC7") (pin "7") (pinfunction "OUT_7") (pintype "output"))
      (node (ref "R36") (pin "1") (pinfunction "1_1") (pintype "passive"))
      (node (ref "R37") (pin "2") (pinfunction "2_2") (pintype "passive"))
      (node (ref "R57") (pin "2") (pinfunction "2_2") (pintype "passive"))
    )
    (net (code "40") (name "Net-(IC7C-+IN)") (class "Default")
      (node (ref "IC7") (pin "10") (pinfunction "+IN_10") (pintype "input"))
      (node (ref "R37") (pin "1") (pinfunction "1_1") (pintype "passive"))
      (node (ref "R39") (pin "1") (pinfunction "1_1") (pintype "passive"))
    )
    (net (code "41") (name "Net-(IC7C--IN)") (class "Default")
      (node (ref "IC7") (pin "9") (pinfunction "-IN_9") (pintype "input"))
      (node (ref "LED102") (pin "A") (pinfunction "A_A") (pintype "passive"))
      (node (ref "R38") (pin "1") (pinfunction "1_1") (pintype "passive"))
    )
    (net (code "42") (name "Net-(IC7C-OUT)") (class "Default")
      (node (ref "IC7") (pin "8") (pinfunction "OUT_8") (pintype "output"))
      (node (ref "LED102") (pin "K") (pinfunction "C_K") (pintype "passive"))
    )
    (net (code "43") (name "Net-(IC7D--IN)") (class "Default")
      (node (ref "IC7") (pin "13") (pinfunction "-IN_13") (pintype "input"))
      (node (ref "R33") (pin "2") (pinfunction "2_2") (pintype "passive"))
      (node (ref "R56") (pin "1") (pinfunction "1_1") (pintype "passive"))
    )
    (net (code "44") (name "Net-(IC8A-OUT)") (class "Default")
      (node (ref "IC8") (pin "1") (pinfunction "OUT_1") (pintype "output"))
      (node (ref "R41") (pin "1") (pinfunction "1_1") (pintype "passive"))
      (node (ref "R45") (pin "2") (pinfunction "2_2") (pintype "passive"))
    )
    (net (code "45") (name "Net-(IC8B--IN)") (class "Default")
      (node (ref "C28") (pin "1") (pinfunction "1_1") (pintype "passive"))
      (node (ref "IC8") (pin "6") (pinfunction "-IN_6") (pintype "input"))
      (node (ref "R31") (pin "1") (pinfunction "1_1") (pintype "passive"))
      (node (ref "R32") (pin "1") (pinfunction "1_1") (pintype "passive"))
      (node (ref "R45") (pin "1") (pinfunction "1_1") (pintype "passive"))
      (node (ref "R46") (pin "2") (pinfunction "2_2") (pintype "passive"))
    )
    (net (code "46") (name "Net-(IC8B-OUT)") (class "Default")
      (node (ref "C28") (pin "2") (pinfunction "2_2") (pintype "passive"))
      (node (ref "IC8") (pin "7") (pinfunction "OUT_7") (pintype "output"))
      (node (ref "R46") (pin "1") (pinfunction "1_1") (pintype "passive"))
      (node (ref "R51") (pin "2") (pinfunction "2_2") (pintype "passive"))
      (node (ref "R58") (pin "2") (pinfunction "2_2") (pintype "passive"))
    )
    (net (code "47") (name "Net-(IC8C-+IN)") (class "Default")
      (node (ref "IC8") (pin "10") (pinfunction "+IN_10") (pintype "input"))
      (node (ref "R50") (pin "1") (pinfunction "1_1") (pintype "passive"))
      (node (ref "R51") (pin "1") (pinfunction "1_1") (pintype "passive"))
    )
    (net (code "48") (name "Net-(IC8C--IN)") (class "Default")
      (node (ref "IC8") (pin "9") (pinfunction "-IN_9") (pintype "input"))
      (node (ref "LED103") (pin "A") (pinfunction "A_A") (pintype "passive"))
      (node (ref "R47") (pin "1") (pinfunction "1_1") (pintype "passive"))
    )
    (net (code "49") (name "Net-(IC8C-OUT)") (class "Default")
      (node (ref "IC8") (pin "8") (pinfunction "OUT_8") (pintype "output"))
      (node (ref "LED103") (pin "K") (pinfunction "C_K") (pintype "passive"))
    )
    (net (code "50") (name "Net-(IC8D--IN)") (class "Default")
      (node (ref "IC8") (pin "13") (pinfunction "-IN_13") (pintype "input"))
      (node (ref "R42") (pin "2") (pinfunction "2_2") (pintype "passive"))
      (node (ref "R55") (pin "1") (pinfunction "1_1") (pintype "passive"))
    )
    (net (code "51") (name "Net-(J100-3)") (class "Default")
      (node (ref "J100") (pin "P3") (pinfunction "3_P3") (pintype "passive"))
      (node (ref "R44") (pin "2") (pinfunction "2_2") (pintype "passive"))
    )
    (net (code "52") (name "Net-(J101-3)") (class "Default")
      (node (ref "J101") (pin "P3") (pinfunction "3_P3") (pintype "passive"))
      (node (ref "R43") (pin "2") (pinfunction "2_2") (pintype "passive"))
    )
    (net (code "53") (name "Net-(J102-2)") (class "Default")
      (node (ref "J102") (pin "P2") (pinfunction "2_P2") (pintype "passive"))
      (node (ref "R54") (pin "2") (pinfunction "2_2") (pintype "passive"))
    )
    (net (code "54") (name "Net-(J102-3)") (class "Default")
      (node (ref "J102") (pin "P3") (pinfunction "3_P3") (pintype "passive"))
      (node (ref "R48") (pin "2") (pinfunction "2_2") (pintype "passive"))
    )
    (net (code "55") (name "Net-(J103-2)") (class "Default")
      (node (ref "J103") (pin "P2") (pinfunction "2_P2") (pintype "passive"))
      (node (ref "R53") (pin "2") (pinfunction "2_2") (pintype "passive"))
    )
    (net (code "56") (name "Net-(J103-3)") (class "Default")
      (node (ref "J103") (pin "P3") (pinfunction "3_P3") (pintype "passive"))
      (node (ref "R49") (pin "2") (pinfunction "2_2") (pintype "passive"))
    )
    (net (code "57") (name "Net-(J104-2)") (class "Default")
      (node (ref "J104") (pin "P2") (pinfunction "2_P2") (pintype "passive"))
      (node (ref "R56") (pin "2") (pinfunction "2_2") (pintype "passive"))
    )
    (net (code "58") (name "Net-(J104-3)") (class "Default")
      (node (ref "J104") (pin "P3") (pinfunction "3_P3") (pintype "passive"))
      (node (ref "R57") (pin "1") (pinfunction "1_1") (pintype "passive"))
    )
    (net (code "59") (name "Net-(J105-2)") (class "Default")
      (node (ref "J105") (pin "P2") (pinfunction "2_P2") (pintype "passive"))
      (node (ref "R55") (pin "2") (pinfunction "2_2") (pintype "passive"))
    )
    (net (code "60") (name "Net-(J105-3)") (class "Default")
      (node (ref "J105") (pin "P3") (pinfunction "3_P3") (pintype "passive"))
      (node (ref "R58") (pin "1") (pinfunction "1_1") (pintype "passive"))
    )
    (net (code "61") (name "Net-(JP1-Pad10)") (class "Default")
      (node (ref "JP1") (pin "10") (pinfunction "10_10") (pintype "passive"))
      (node (ref "JP1") (pin "9") (pinfunction "9_9") (pintype "passive"))
      (node (ref "P1") (pin "2") (pinfunction "2_2") (pintype "bidirectional"))
    )
    (net (code "62") (name "Net-(L1-Pad2)") (class "Default")
      (node (ref "L1") (pin "2") (pinfunction "2_2") (pintype "passive"))
      (node (ref "P1") (pin "1") (pinfunction "1_1") (pintype "bidirectional"))
    )
    (net (code "63") (name "Net-(POT100-W)") (class "Default")
      (node (ref "POT100") (pin "2") (pinfunction "W_2") (pintype "passive"))
      (node (ref "R44") (pin "1") (pinfunction "1_1") (pintype "passive"))
    )
    (net (code "64") (name "Net-(POT101-W)") (class "Default")
      (node (ref "POT101") (pin "2") (pinfunction "W_2") (pintype "passive"))
      (node (ref "R43") (pin "1") (pinfunction "1_1") (pintype "passive"))
    )
    (net (code "65") (name "Net-(R100-S)") (class "Default")
      (node (ref "R100") (pin "P$2") (pinfunction "S_P$2") (pintype "passive"))
      (node (ref "R2") (pin "1") (pinfunction "1_1") (pintype "passive"))
    )
    (net (code "66") (name "Net-(R101-S)") (class "Default")
      (node (ref "R101") (pin "P$2") (pinfunction "S_P$2") (pintype "passive"))
      (node (ref "R12") (pin "1") (pinfunction "1_1") (pintype "passive"))
    )
    (net (code "67") (name "OUT") (class "Default")
      (node (ref "IC8") (pin "14") (pinfunction "OUT_14") (pintype "output"))
      (node (ref "J1") (pin "1") (pinfunction "1_1") (pintype "passive"))
      (node (ref "R42") (pin "1") (pinfunction "1_1") (pintype "passive"))
    )
    (net (code "68") (name "VCC") (class "Default")
      (node (ref "C1") (pin "1") (pinfunction "1_1") (pintype "passive"))
      (node (ref "C16") (pin "1") (pinfunction "1_1") (pintype "passive"))
      (node (ref "C18") (pin "1") (pinfunction "1_1") (pintype "passive"))
      (node (ref "C23") (pin "1") (pinfunction "1_1") (pintype "passive"))
      (node (ref "C26") (pin "1") (pinfunction "1_1") (pintype "passive"))
      (node (ref "C4") (pin "+") (pinfunction "+_+") (pintype "passive"))
      (node (ref "C7") (pin "1") (pinfunction "1_1") (pintype "passive"))
      (node (ref "IC3") (pin "16") (pinfunction "V+_16") (pintype "power_in"))
      (node (ref "IC5") (pin "4") (pinfunction "V+_4") (pintype "power_in"))
      (node (ref "IC6") (pin "4") (pinfunction "V+_4") (pintype "power_in"))
      (node (ref "IC7") (pin "4") (pinfunction "V+_4") (pintype "power_in"))
      (node (ref "IC8") (pin "4") (pinfunction "V+_4") (pintype "power_in"))
      (node (ref "L2") (pin "1") (pinfunction "1_1") (pintype "passive"))
      (node (ref "R3") (pin "1") (pinfunction "1_1") (pintype "passive"))
      (node (ref "R5") (pin "1") (pinfunction "1_1") (pintype "passive"))
    )
    (net (code "69") (name "VEE") (class "Default")
      (node (ref "C10") (pin "2") (pinfunction "2_2") (pintype "passive"))
      (node (ref "C14") (pin "2") (pinfunction "2_2") (pintype "passive"))
      (node (ref "C17") (pin "2") (pinfunction "2_2") (pintype "passive"))
      (node (ref "C24") (pin "2") (pinfunction "2_2") (pintype "passive"))
      (node (ref "C27") (pin "2") (pinfunction "2_2") (pintype "passive"))
      (node (ref "C3") (pin "1") (pinfunction "1_1") (pintype "passive"))
      (node (ref "C6") (pin "-") (pinfunction "-_-") (pintype "passive"))
      (node (ref "D2") (pin "A") (pinfunction "A_A") (pintype "passive"))
      (node (ref "IC3") (pin "9") (pinfunction "V-_9") (pintype "power_in"))
      (node (ref "IC5") (pin "11") (pinfunction "V-_11") (pintype "power_in"))
      (node (ref "IC6") (pin "11") (pinfunction "V-_11") (pintype "power_in"))
      (node (ref "IC7") (pin "11") (pinfunction "V-_11") (pintype "power_in"))
      (node (ref "IC8") (pin "11") (pinfunction "V-_11") (pintype "power_in"))
      (node (ref "L1") (pin "1") (pinfunction "1_1") (pintype "passive"))
      (node (ref "R1") (pin "1") (pinfunction "1_1") (pintype "passive"))
    )
  )
)
